# p3_keypad_encoder_led.net
KiCad netlist of a schematic drawn in Altium Designer
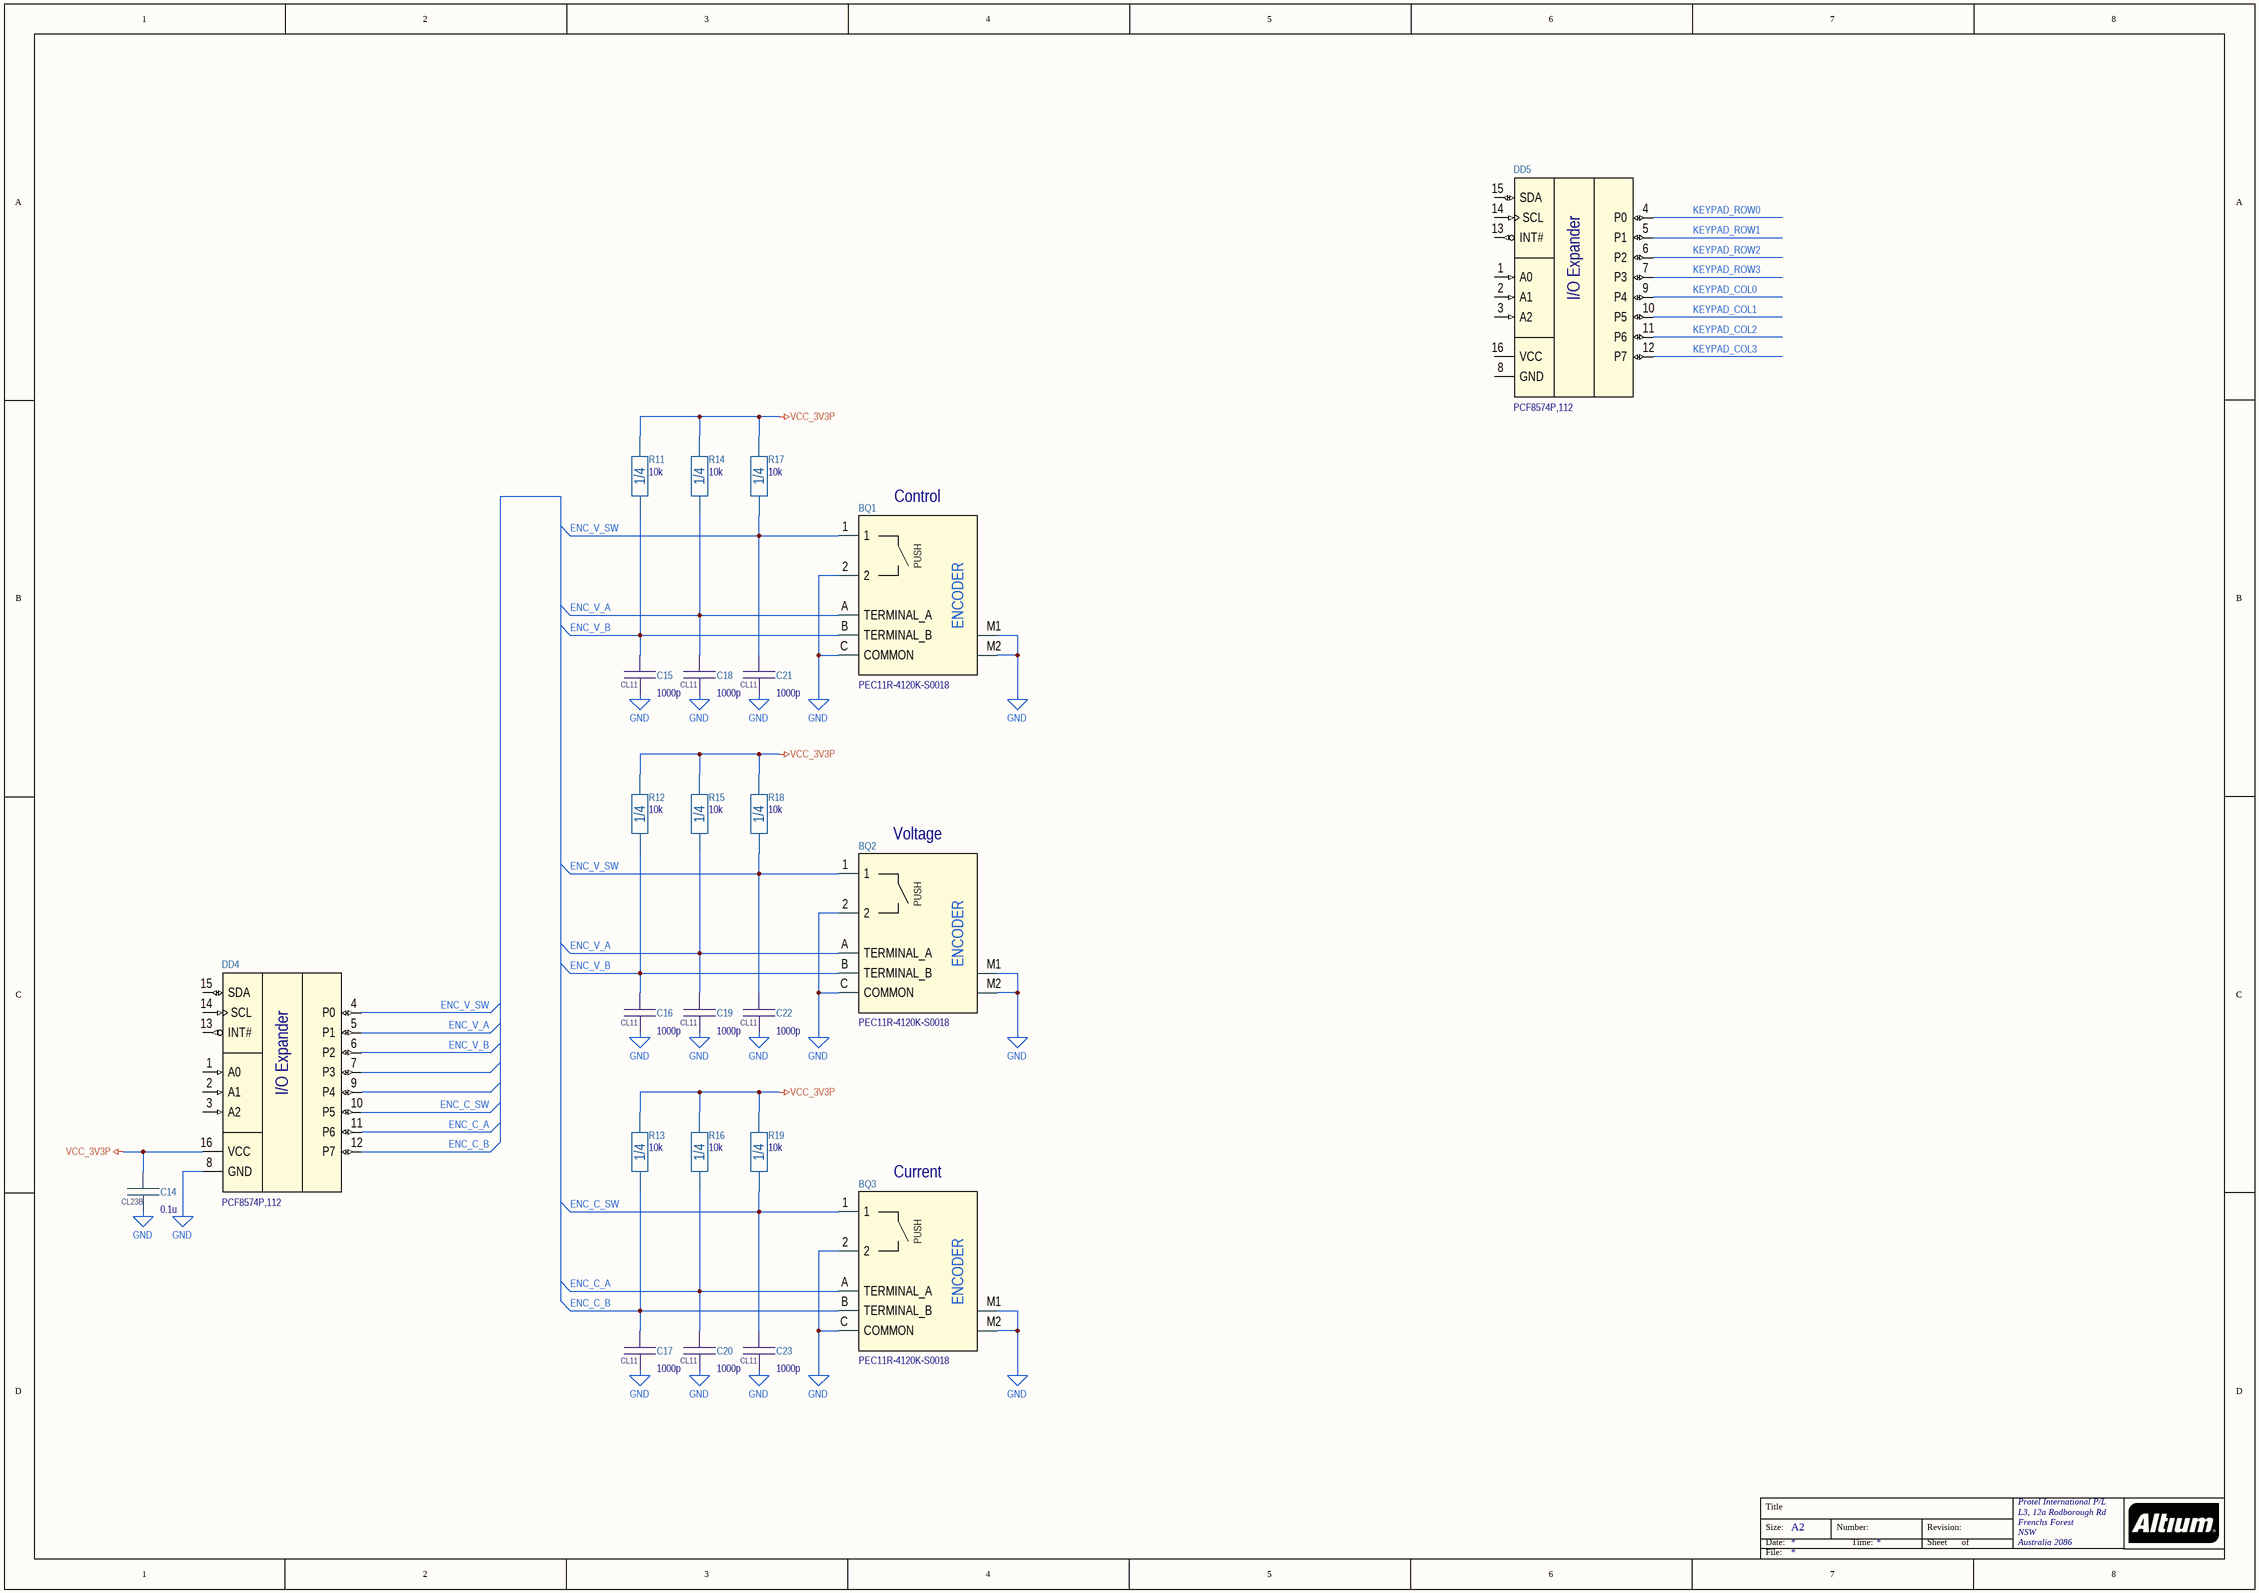
[diagram p0: p3_keypad_encoder_led.SchDoc]

(export (version "E")
  (design (tool "Eeschema 10.0.6"))
  (components
    (comp (ref "BQ1")
      (value "PEC11R-4120K-S0018")
      (footprint "PcbLib_Others:PEC11R-4120K-S0018")
      (description "12 mm Incremental Encoder")
      (fields (field (name "MANUFACTURER") "Bourns Inc."))
      (libsource (lib "Schlib_Bourns") (part "PEC11R-4120K-S0018"))
    )
    (comp (ref "BQ2")
      (value "PEC11R-4120K-S0018")
      (footprint "PcbLib_Others:PEC11R-4120K-S0018")
      (description "12 mm Incremental Encoder")
      (fields (field (name "MANUFACTURER") "Bourns Inc."))
      (libsource (lib "Schlib_Bourns") (part "PEC11R-4120K-S0018"))
    )
    (comp (ref "BQ3")
      (value "PEC11R-4120K-S0018")
      (footprint "PcbLib_Others:PEC11R-4120K-S0018")
      (description "12 mm Incremental Encoder")
      (fields (field (name "MANUFACTURER") "Bourns Inc."))
      (libsource (lib "Schlib_Bourns") (part "PEC11R-4120K-S0018"))
    )
    (comp (ref "C14")
      (value "0.1u")
      (footprint "PcbLib_RC:CL23B_7.2x2.5")
      (description "Box-type metallized polyester film capacitor")
      (fields
        (field (name "TOLERANCE") "± * %")
        (field (name "VOLTAGE") "63V")
        (field (name "PACKAGE") "CL23B")
      )
      (libsource (lib "Schlib_RC") (part "CL23B"))
    )
    (comp (ref "C15")
      (value "1000p")
      (footprint "PcbLib_RC:CL11_6x3.5_P3.5")
      (description "CL11 Type Polyester Film Metal Foil Capacitor-inductive")
      (fields
        (field (name "TOLERANCE") "± 5 %")
        (field (name "VOLTAGE") "100V")
        (field (name "PACKAGE") "CL11")
      )
      (libsource (lib "Schlib_RC") (part "CL11"))
    )
    (comp (ref "C16")
      (value "1000p")
      (footprint "PcbLib_RC:CL11_6x3.5_P3.5")
      (description "CL11 Type Polyester Film Metal Foil Capacitor-inductive")
      (fields
        (field (name "TOLERANCE") "± 5 %")
        (field (name "VOLTAGE") "100V")
        (field (name "PACKAGE") "CL11")
      )
      (libsource (lib "Schlib_RC") (part "CL11"))
    )
    (comp (ref "C17")
      (value "1000p")
      (footprint "PcbLib_RC:CL11_6x3.5_P3.5")
      (description "CL11 Type Polyester Film Metal Foil Capacitor-inductive")
      (fields
        (field (name "TOLERANCE") "± 5 %")
        (field (name "VOLTAGE") "100V")
        (field (name "PACKAGE") "CL11")
      )
      (libsource (lib "Schlib_RC") (part "CL11"))
    )
    (comp (ref "C18")
      (value "1000p")
      (footprint "PcbLib_RC:CL11_6x3.5_P3.5")
      (description "CL11 Type Polyester Film Metal Foil Capacitor-inductive")
      (fields
        (field (name "TOLERANCE") "± 5 %")
        (field (name "VOLTAGE") "100V")
        (field (name "PACKAGE") "CL11")
      )
      (libsource (lib "Schlib_RC") (part "CL11"))
    )
    (comp (ref "C19")
      (value "1000p")
      (footprint "PcbLib_RC:CL11_6x3.5_P3.5")
      (description "CL11 Type Polyester Film Metal Foil Capacitor-inductive")
      (fields
        (field (name "TOLERANCE") "± 5 %")
        (field (name "VOLTAGE") "100V")
        (field (name "PACKAGE") "CL11")
      )
      (libsource (lib "Schlib_RC") (part "CL11"))
    )
    (comp (ref "C20")
      (value "1000p")
      (footprint "PcbLib_RC:CL11_6x3.5_P3.5")
      (description "CL11 Type Polyester Film Metal Foil Capacitor-inductive")
      (fields
        (field (name "TOLERANCE") "± 5 %")
        (field (name "VOLTAGE") "100V")
        (field (name "PACKAGE") "CL11")
      )
      (libsource (lib "Schlib_RC") (part "CL11"))
    )
    (comp (ref "C21")
      (value "1000p")
      (footprint "PcbLib_RC:CL11_6x3.5_P3.5")
      (description "CL11 Type Polyester Film Metal Foil Capacitor-inductive")
      (fields
        (field (name "TOLERANCE") "± 5 %")
        (field (name "VOLTAGE") "100V")
        (field (name "PACKAGE") "CL11")
      )
      (libsource (lib "Schlib_RC") (part "CL11"))
    )
    (comp (ref "C22")
      (value "1000p")
      (footprint "PcbLib_RC:CL11_6x3.5_P3.5")
      (description "CL11 Type Polyester Film Metal Foil Capacitor-inductive")
      (fields
        (field (name "TOLERANCE") "± 5 %")
        (field (name "VOLTAGE") "100V")
        (field (name "PACKAGE") "CL11")
      )
      (libsource (lib "Schlib_RC") (part "CL11"))
    )
    (comp (ref "C23")
      (value "1000p")
      (footprint "PcbLib_RC:CL11_6x3.5_P3.5")
      (description "CL11 Type Polyester Film Metal Foil Capacitor-inductive")
      (fields
        (field (name "TOLERANCE") "± 5 %")
        (field (name "VOLTAGE") "100V")
        (field (name "PACKAGE") "CL11")
      )
      (libsource (lib "Schlib_RC") (part "CL11"))
    )
    (comp (ref "DD4")
      (value "PCF8574P,112")
      (footprint "PcbLib_ICs:DIP-16P-M03")
      (description "Remote 8-bit I/O expander for I2C-bus")
      (fields (field (name "MANUFACTURER") "NXP USA Inc."))
      (libsource (lib "Schlib_NXP_Semiconductors") (part "PCF8574P,112"))
    )
    (comp (ref "DD5")
      (value "PCF8574P,112")
      (footprint "PcbLib_ICs:DIP-16P-M03")
      (description "Remote 8-bit I/O expander for I2C-bus")
      (fields (field (name "MANUFACTURER") "NXP USA Inc."))
      (libsource (lib "Schlib_NXP_Semiconductors") (part "PCF8574P,112"))
    )
    (comp (ref "R11")
      (value "10k")
      (footprint "PcbLib_RC:CFR-25")
      (description "Resistor 1/4W")
      (fields
        (field (name "TOLERANCE") "± 1 %")
        (field (name "PART NUMBER") "MFR-25FTF52-10K")
        (field (name "PACKAGE") "1/4")
      )
      (libsource (lib "Schlib_RC") (part "CF25"))
    )
    (comp (ref "R12")
      (value "10k")
      (footprint "PcbLib_RC:CFR-25")
      (description "Resistor 1/4W")
      (fields
        (field (name "TOLERANCE") "± 1 %")
        (field (name "PART NUMBER") "MFR-25FTF52-10K")
        (field (name "PACKAGE") "1/4")
      )
      (libsource (lib "Schlib_RC") (part "CF25"))
    )
    (comp (ref "R13")
      (value "10k")
      (footprint "PcbLib_RC:CFR-25")
      (description "Resistor 1/4W")
      (fields
        (field (name "TOLERANCE") "± 1 %")
        (field (name "PART NUMBER") "MFR-25FTF52-10K")
        (field (name "PACKAGE") "1/4")
      )
      (libsource (lib "Schlib_RC") (part "CF25"))
    )
    (comp (ref "R14")
      (value "10k")
      (footprint "PcbLib_RC:CFR-25")
      (description "Resistor 1/4W")
      (fields
        (field (name "TOLERANCE") "± 1 %")
        (field (name "PART NUMBER") "MFR-25FTF52-10K")
        (field (name "PACKAGE") "1/4")
      )
      (libsource (lib "Schlib_RC") (part "CF25"))
    )
    (comp (ref "R15")
      (value "10k")
      (footprint "PcbLib_RC:CFR-25")
      (description "Resistor 1/4W")
      (fields
        (field (name "TOLERANCE") "± 1 %")
        (field (name "PART NUMBER") "MFR-25FTF52-10K")
        (field (name "PACKAGE") "1/4")
      )
      (libsource (lib "Schlib_RC") (part "CF25"))
    )
    (comp (ref "R16")
      (value "10k")
      (footprint "PcbLib_RC:CFR-25")
      (description "Resistor 1/4W")
      (fields
        (field (name "TOLERANCE") "± 1 %")
        (field (name "PART NUMBER") "MFR-25FTF52-10K")
        (field (name "PACKAGE") "1/4")
      )
      (libsource (lib "Schlib_RC") (part "CF25"))
    )
    (comp (ref "R17")
      (value "10k")
      (footprint "PcbLib_RC:CFR-25")
      (description "Resistor 1/4W")
      (fields
        (field (name "TOLERANCE") "± 1 %")
        (field (name "PART NUMBER") "MFR-25FTF52-10K")
        (field (name "PACKAGE") "1/4")
      )
      (libsource (lib "Schlib_RC") (part "CF25"))
    )
    (comp (ref "R18")
      (value "10k")
      (footprint "PcbLib_RC:CFR-25")
      (description "Resistor 1/4W")
      (fields
        (field (name "TOLERANCE") "± 1 %")
        (field (name "PART NUMBER") "MFR-25FTF52-10K")
        (field (name "PACKAGE") "1/4")
      )
      (libsource (lib "Schlib_RC") (part "CF25"))
    )
    (comp (ref "R19")
      (value "10k")
      (footprint "PcbLib_RC:CFR-25")
      (description "Resistor 1/4W")
      (fields
        (field (name "TOLERANCE") "± 1 %")
        (field (name "PART NUMBER") "MFR-25FTF52-10K")
        (field (name "PACKAGE") "1/4")
      )
      (libsource (lib "Schlib_RC") (part "CF25"))
    )
  )
  (nets
    (net (code "1") (name "/ENC_C_A") (class "Default")
      (node (ref "BQ3") (pin "A") (pinfunction "TERMINAL_A_A") (pintype "passive"))
      (node (ref "C20") (pin "2") (pinfunction "2_2") (pintype "passive"))
      (node (ref "DD4") (pin "11") (pinfunction "P6_11") (pintype "bidirectional"))
      (node (ref "R16") (pin "1") (pinfunction "1_1") (pintype "passive"))
    )
    (net (code "2") (name "/ENC_C_B") (class "Default")
      (node (ref "BQ3") (pin "B") (pinfunction "TERMINAL_B_B") (pintype "passive"))
      (node (ref "C17") (pin "2") (pinfunction "2_2") (pintype "passive"))
      (node (ref "DD4") (pin "12") (pinfunction "P7_12") (pintype "bidirectional"))
      (node (ref "R13") (pin "1") (pinfunction "1_1") (pintype "passive"))
    )
    (net (code "3") (name "/ENC_C_SW") (class "Default")
      (node (ref "BQ3") (pin "1") (pinfunction "1_1") (pintype "passive"))
      (node (ref "C23") (pin "2") (pinfunction "2_2") (pintype "passive"))
      (node (ref "DD4") (pin "10") (pinfunction "P5_10") (pintype "bidirectional"))
      (node (ref "R19") (pin "1") (pinfunction "1_1") (pintype "passive"))
    )
    (net (code "4") (name "/ENC_V_A") (class "Default")
      (node (ref "BQ1") (pin "A") (pinfunction "TERMINAL_A_A") (pintype "passive"))
      (node (ref "BQ2") (pin "A") (pinfunction "TERMINAL_A_A") (pintype "passive"))
      (node (ref "C18") (pin "2") (pinfunction "2_2") (pintype "passive"))
      (node (ref "C19") (pin "2") (pinfunction "2_2") (pintype "passive"))
      (node (ref "DD4") (pin "5") (pinfunction "P1_5") (pintype "bidirectional"))
      (node (ref "R14") (pin "1") (pinfunction "1_1") (pintype "passive"))
      (node (ref "R15") (pin "1") (pinfunction "1_1") (pintype "passive"))
    )
    (net (code "5") (name "/ENC_V_B") (class "Default")
      (node (ref "BQ1") (pin "B") (pinfunction "TERMINAL_B_B") (pintype "passive"))
      (node (ref "BQ2") (pin "B") (pinfunction "TERMINAL_B_B") (pintype "passive"))
      (node (ref "C15") (pin "2") (pinfunction "2_2") (pintype "passive"))
      (node (ref "C16") (pin "2") (pinfunction "2_2") (pintype "passive"))
      (node (ref "DD4") (pin "6") (pinfunction "P2_6") (pintype "bidirectional"))
      (node (ref "R11") (pin "1") (pinfunction "1_1") (pintype "passive"))
      (node (ref "R12") (pin "1") (pinfunction "1_1") (pintype "passive"))
    )
    (net (code "6") (name "/ENC_V_SW") (class "Default")
      (node (ref "BQ1") (pin "1") (pinfunction "1_1") (pintype "passive"))
      (node (ref "BQ2") (pin "1") (pinfunction "1_1") (pintype "passive"))
      (node (ref "C21") (pin "2") (pinfunction "2_2") (pintype "passive"))
      (node (ref "C22") (pin "2") (pinfunction "2_2") (pintype "passive"))
      (node (ref "DD4") (pin "4") (pinfunction "P0_4") (pintype "bidirectional"))
      (node (ref "R17") (pin "1") (pinfunction "1_1") (pintype "passive"))
      (node (ref "R18") (pin "1") (pinfunction "1_1") (pintype "passive"))
    )
    (net (code "7") (name "/KEYPAD_COL0") (class "Default")
      (node (ref "DD5") (pin "9") (pinfunction "P4_9") (pintype "bidirectional"))
    )
    (net (code "8") (name "/KEYPAD_COL1") (class "Default")
      (node (ref "DD5") (pin "10") (pinfunction "P5_10") (pintype "bidirectional"))
    )
    (net (code "9") (name "/KEYPAD_COL2") (class "Default")
      (node (ref "DD5") (pin "11") (pinfunction "P6_11") (pintype "bidirectional"))
    )
    (net (code "10") (name "/KEYPAD_COL3") (class "Default")
      (node (ref "DD5") (pin "12") (pinfunction "P7_12") (pintype "bidirectional"))
    )
    (net (code "11") (name "/KEYPAD_ROW0") (class "Default")
      (node (ref "DD5") (pin "4") (pinfunction "P0_4") (pintype "bidirectional"))
    )
    (net (code "12") (name "/KEYPAD_ROW1") (class "Default")
      (node (ref "DD5") (pin "5") (pinfunction "P1_5") (pintype "bidirectional"))
    )
    (net (code "13") (name "/KEYPAD_ROW2") (class "Default")
      (node (ref "DD5") (pin "6") (pinfunction "P2_6") (pintype "bidirectional"))
    )
    (net (code "14") (name "/KEYPAD_ROW3") (class "Default")
      (node (ref "DD5") (pin "7") (pinfunction "P3_7") (pintype "bidirectional"))
    )
    (net (code "15") (name "GND") (class "Default")
      (node (ref "BQ1") (pin "2") (pinfunction "2_2") (pintype "passive"))
      (node (ref "BQ1") (pin "C") (pinfunction "COMMON_C") (pintype "passive"))
      (node (ref "BQ1") (pin "M1") (pinfunction "MECHANICAL1_M1") (pintype "passive"))
      (node (ref "BQ1") (pin "M2") (pinfunction "MECHANICAL2_M2") (pintype "passive"))
      (node (ref "BQ2") (pin "2") (pinfunction "2_2") (pintype "passive"))
      (node (ref "BQ2") (pin "C") (pinfunction "COMMON_C") (pintype "passive"))
      (node (ref "BQ2") (pin "M1") (pinfunction "MECHANICAL1_M1") (pintype "passive"))
      (node (ref "BQ2") (pin "M2") (pinfunction "MECHANICAL2_M2") (pintype "passive"))
      (node (ref "BQ3") (pin "2") (pinfunction "2_2") (pintype "passive"))
      (node (ref "BQ3") (pin "C") (pinfunction "COMMON_C") (pintype "passive"))
      (node (ref "BQ3") (pin "M1") (pinfunction "MECHANICAL1_M1") (pintype "passive"))
      (node (ref "BQ3") (pin "M2") (pinfunction "MECHANICAL2_M2") (pintype "passive"))
      (node (ref "C14") (pin "2") (pinfunction "2_2") (pintype "passive"))
      (node (ref "C15") (pin "1") (pinfunction "1_1") (pintype "passive"))
      (node (ref "C16") (pin "1") (pinfunction "1_1") (pintype "passive"))
      (node (ref "C17") (pin "1") (pinfunction "1_1") (pintype "passive"))
      (node (ref "C18") (pin "1") (pinfunction "1_1") (pintype "passive"))
      (node (ref "C19") (pin "1") (pinfunction "1_1") (pintype "passive"))
      (node (ref "C20") (pin "1") (pinfunction "1_1") (pintype "passive"))
      (node (ref "C21") (pin "1") (pinfunction "1_1") (pintype "passive"))
      (node (ref "C22") (pin "1") (pinfunction "1_1") (pintype "passive"))
      (node (ref "C23") (pin "1") (pinfunction "1_1") (pintype "passive"))
      (node (ref "DD4") (pin "8") (pinfunction "GND_8") (pintype "power_in"))
    )
    (net (code "16") (name "VCC_3V3P") (class "Default")
      (node (ref "C14") (pin "1") (pinfunction "1_1") (pintype "passive"))
      (node (ref "DD4") (pin "16") (pinfunction "VCC_16") (pintype "power_in"))
      (node (ref "R11") (pin "2") (pinfunction "2_2") (pintype "passive"))
      (node (ref "R12") (pin "2") (pinfunction "2_2") (pintype "passive"))
      (node (ref "R13") (pin "2") (pinfunction "2_2") (pintype "passive"))
      (node (ref "R14") (pin "2") (pinfunction "2_2") (pintype "passive"))
      (node (ref "R15") (pin "2") (pinfunction "2_2") (pintype "passive"))
      (node (ref "R16") (pin "2") (pinfunction "2_2") (pintype "passive"))
      (node (ref "R17") (pin "2") (pinfunction "2_2") (pintype "passive"))
      (node (ref "R18") (pin "2") (pinfunction "2_2") (pintype "passive"))
      (node (ref "R19") (pin "2") (pinfunction "2_2") (pintype "passive"))
    )
    (net (code "17") (name "unconnected-(DD4-A0-Pad1)") (class "Default")
      (node (ref "DD4") (pin "1") (pinfunction "A0_1") (pintype "input"))
    )
    (net (code "18") (name "unconnected-(DD4-A1-Pad2)") (class "Default")
      (node (ref "DD4") (pin "2") (pinfunction "A1_2") (pintype "input"))
    )
    (net (code "19") (name "unconnected-(DD4-A2-Pad3)") (class "Default")
      (node (ref "DD4") (pin "3") (pinfunction "A2_3") (pintype "input"))
    )
    (net (code "20") (name "unconnected-(DD4-INT#-Pad13)") (class "Default")
      (node (ref "DD4") (pin "13") (pinfunction "INT#_13") (pintype "output"))
    )
    (net (code "21") (name "unconnected-(DD4-P3-Pad7)") (class "Default")
      (node (ref "DD4") (pin "7") (pinfunction "P3_7") (pintype "bidirectional"))
    )
    (net (code "22") (name "unconnected-(DD4-P4-Pad9)") (class "Default")
      (node (ref "DD4") (pin "9") (pinfunction "P4_9") (pintype "bidirectional"))
    )
    (net (code "23") (name "unconnected-(DD4-SCL-Pad14)") (class "Default")
      (node (ref "DD4") (pin "14") (pinfunction "SCL_14") (pintype "input"))
    )
    (net (code "24") (name "unconnected-(DD4-SDA-Pad15)") (class "Default")
      (node (ref "DD4") (pin "15") (pinfunction "SDA_15") (pintype "bidirectional"))
    )
    (net (code "25") (name "unconnected-(DD5-A0-Pad1)") (class "Default")
      (node (ref "DD5") (pin "1") (pinfunction "A0_1") (pintype "input"))
    )
    (net (code "26") (name "unconnected-(DD5-A1-Pad2)") (class "Default")
      (node (ref "DD5") (pin "2") (pinfunction "A1_2") (pintype "input"))
    )
    (net (code "27") (name "unconnected-(DD5-A2-Pad3)") (class "Default")
      (node (ref "DD5") (pin "3") (pinfunction "A2_3") (pintype "input"))
    )
    (net (code "28") (name "unconnected-(DD5-GND-Pad8)") (class "Default")
      (node (ref "DD5") (pin "8") (pinfunction "GND_8") (pintype "power_in"))
    )
    (net (code "29") (name "unconnected-(DD5-INT#-Pad13)") (class "Default")
      (node (ref "DD5") (pin "13") (pinfunction "INT#_13") (pintype "output"))
    )
    (net (code "30") (name "unconnected-(DD5-SCL-Pad14)") (class "Default")
      (node (ref "DD5") (pin "14") (pinfunction "SCL_14") (pintype "input"))
    )
    (net (code "31") (name "unconnected-(DD5-SDA-Pad15)") (class "Default")
      (node (ref "DD5") (pin "15") (pinfunction "SDA_15") (pintype "bidirectional"))
    )
    (net (code "32") (name "unconnected-(DD5-VCC-Pad16)") (class "Default")
      (node (ref "DD5") (pin "16") (pinfunction "VCC_16") (pintype "power_in"))
    )
  )
)
